# Single_LED.net
KiCad netlist of a schematic drawn in Altium Designer
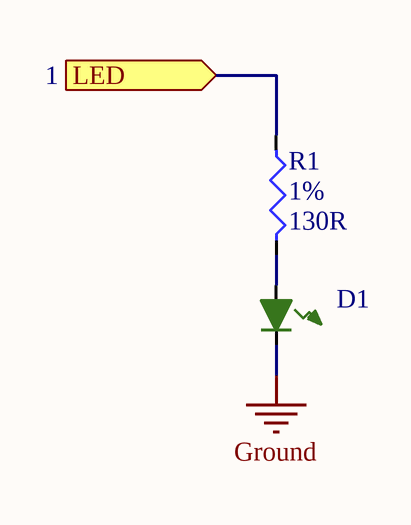
[diagram p0: Single LED.SchDoc]

(export (version "E")
  (design (tool "Eeschema 10.0.6"))
  (components
    (comp (ref "D1")
      (value "LED Green 0603 Signal 571nm")
      (footprint "0603 LED Green")
      (fields
        (field (name "MANUFACTURER") "Lite-On Inc.")
        (field (name "MANUFACTURER PART NUMBER") "LTST-C191KGKT")
      )
      (libsource (lib "Integrated Library") (part "LED Green 0603 Signal 571nm"))
    )
    (comp (ref "R1")
      (value "Resistor 130R 0603 1%")
      (footprint "0603 Resistor")
      (fields
        (field (name "MANUFACTURER") "Yageo")
        (field (name "MANUFACTURER PART NUMBER") "RC0603FR-07130RL")
        (field (name "TOLERANCE") "1%")
        (field (name "RESISTANCE") "130R")
      )
      (libsource (lib "Integrated Library") (part "Resistor 130R 0603 1%"))
    )
  )
  (nets
    (net (code "1") (name "/LED") (class "Default")
      (node (ref "R1") (pin "2") (pinfunction "2_2") (pintype "passive"))
    )
    (net (code "2") (name "Ground") (class "Default")
      (node (ref "D1") (pin "2") (pinfunction "2_2") (pintype "passive"))
    )
    (net (code "3") (name "Net-(D1-Pad1)") (class "Default")
      (node (ref "D1") (pin "1") (pinfunction "1_1") (pintype "passive"))
      (node (ref "R1") (pin "1") (pinfunction "1_1") (pintype "passive"))
    )
  )
)
